# filter.net
KiCad netlist of a schematic drawn in EAGLE
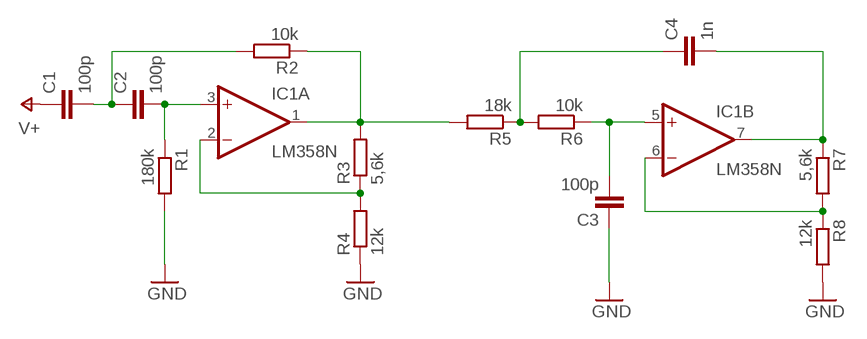
[diagram p0: schematic, sheet 1]

(export (version "E")
  (design (tool "Eeschema 10.0.6"))
  (components
    (comp (ref "C1")
      (value "100p")
      (footprint "eagle-import:C050-024X044")
      (libsource (lib "eagle-import") (part "C-EU050-024X044"))
    )
    (comp (ref "C2")
      (value "100p")
      (footprint "eagle-import:C050-024X044")
      (libsource (lib "eagle-import") (part "C-EU050-024X044"))
    )
    (comp (ref "C3")
      (value "100p")
      (footprint "eagle-import:C050-024X044")
      (libsource (lib "eagle-import") (part "C-EU050-024X044"))
    )
    (comp (ref "C4")
      (value "1n")
      (footprint "eagle-import:C050-024X044")
      (libsource (lib "eagle-import") (part "C-EU050-024X044"))
    )
    (comp (ref "IC1")
      (value "LM358N")
      (footprint "eagle-import:DIL08")
      (libsource (lib "eagle-import") (part "LM358N"))
    )
    (comp (ref "R1")
      (value "180k")
      (footprint "eagle-import:0207_10")
      (libsource (lib "eagle-import") (part "R-EU_0207/10"))
    )
    (comp (ref "R2")
      (value "10k")
      (footprint "eagle-import:0207_10")
      (libsource (lib "eagle-import") (part "R-EU_0207/10"))
    )
    (comp (ref "R3")
      (value "5,6k")
      (footprint "eagle-import:0207_10")
      (libsource (lib "eagle-import") (part "R-EU_0207/10"))
    )
    (comp (ref "R4")
      (value "12k")
      (footprint "eagle-import:0207_10")
      (libsource (lib "eagle-import") (part "R-EU_0207/10"))
    )
    (comp (ref "R5")
      (value "18k")
      (footprint "eagle-import:0207_10")
      (libsource (lib "eagle-import") (part "R-EU_0207/10"))
    )
    (comp (ref "R6")
      (value "10k")
      (footprint "eagle-import:0207_10")
      (libsource (lib "eagle-import") (part "R-EU_0207/10"))
    )
    (comp (ref "R7")
      (value "5,6k")
      (footprint "eagle-import:0207_10")
      (libsource (lib "eagle-import") (part "R-EU_0207/10"))
    )
    (comp (ref "R8")
      (value "12k")
      (footprint "eagle-import:0207_10")
      (libsource (lib "eagle-import") (part "R-EU_0207/10"))
    )
  )
  (nets
    (net (code "1") (name "GND") (class "Default")
      (node (ref "C3") (pin "1") (pinfunction "1_1") (pintype "passive"))
      (node (ref "R1") (pin "2") (pinfunction "2_2") (pintype "passive"))
      (node (ref "R4") (pin "1") (pinfunction "1_1") (pintype "passive"))
      (node (ref "R8") (pin "2") (pinfunction "2_2") (pintype "passive"))
    )
    (net (code "2") (name "Net-(C1-Pad2)") (class "Default")
      (node (ref "C1") (pin "2") (pinfunction "2_2") (pintype "passive"))
      (node (ref "C2") (pin "1") (pinfunction "1_1") (pintype "passive"))
      (node (ref "R2") (pin "2") (pinfunction "2_2") (pintype "passive"))
    )
    (net (code "3") (name "Net-(C4-Pad1)") (class "Default")
      (node (ref "C4") (pin "1") (pinfunction "1_1") (pintype "passive"))
      (node (ref "R5") (pin "1") (pinfunction "1_1") (pintype "passive"))
      (node (ref "R6") (pin "2") (pinfunction "2_2") (pintype "passive"))
    )
    (net (code "4") (name "Net-(IC1A-+IN)") (class "Default")
      (node (ref "C2") (pin "2") (pinfunction "2_2") (pintype "passive"))
      (node (ref "IC1") (pin "3") (pinfunction "+IN_3") (pintype "input"))
      (node (ref "R1") (pin "1") (pinfunction "1_1") (pintype "passive"))
    )
    (net (code "5") (name "Net-(IC1A--IN)") (class "Default")
      (node (ref "IC1") (pin "2") (pinfunction "-IN_2") (pintype "input"))
      (node (ref "R3") (pin "1") (pinfunction "1_1") (pintype "passive"))
      (node (ref "R4") (pin "2") (pinfunction "2_2") (pintype "passive"))
    )
    (net (code "6") (name "Net-(IC1A-OUT)") (class "Default")
      (node (ref "IC1") (pin "1") (pinfunction "OUT_1") (pintype "output"))
      (node (ref "R2") (pin "1") (pinfunction "1_1") (pintype "passive"))
      (node (ref "R3") (pin "2") (pinfunction "2_2") (pintype "passive"))
      (node (ref "R5") (pin "2") (pinfunction "2_2") (pintype "passive"))
    )
    (net (code "7") (name "Net-(IC1B-+IN)") (class "Default")
      (node (ref "C3") (pin "2") (pinfunction "2_2") (pintype "passive"))
      (node (ref "IC1") (pin "5") (pinfunction "+IN_5") (pintype "input"))
      (node (ref "R6") (pin "1") (pinfunction "1_1") (pintype "passive"))
    )
    (net (code "8") (name "Net-(IC1B--IN)") (class "Default")
      (node (ref "IC1") (pin "6") (pinfunction "-IN_6") (pintype "input"))
      (node (ref "R7") (pin "2") (pinfunction "2_2") (pintype "passive"))
      (node (ref "R8") (pin "1") (pinfunction "1_1") (pintype "passive"))
    )
    (net (code "9") (name "Net-(IC1B-OUT)") (class "Default")
      (node (ref "C4") (pin "2") (pinfunction "2_2") (pintype "passive"))
      (node (ref "IC1") (pin "7") (pinfunction "OUT_7") (pintype "output"))
      (node (ref "R7") (pin "1") (pinfunction "1_1") (pintype "passive"))
    )
    (net (code "10") (name "V+") (class "Default")
      (node (ref "C1") (pin "1") (pinfunction "1_1") (pintype "passive"))
    )
  )
)
